# ADSR_7555_MAIN.net
KiCad netlist of a schematic drawn in EAGLE
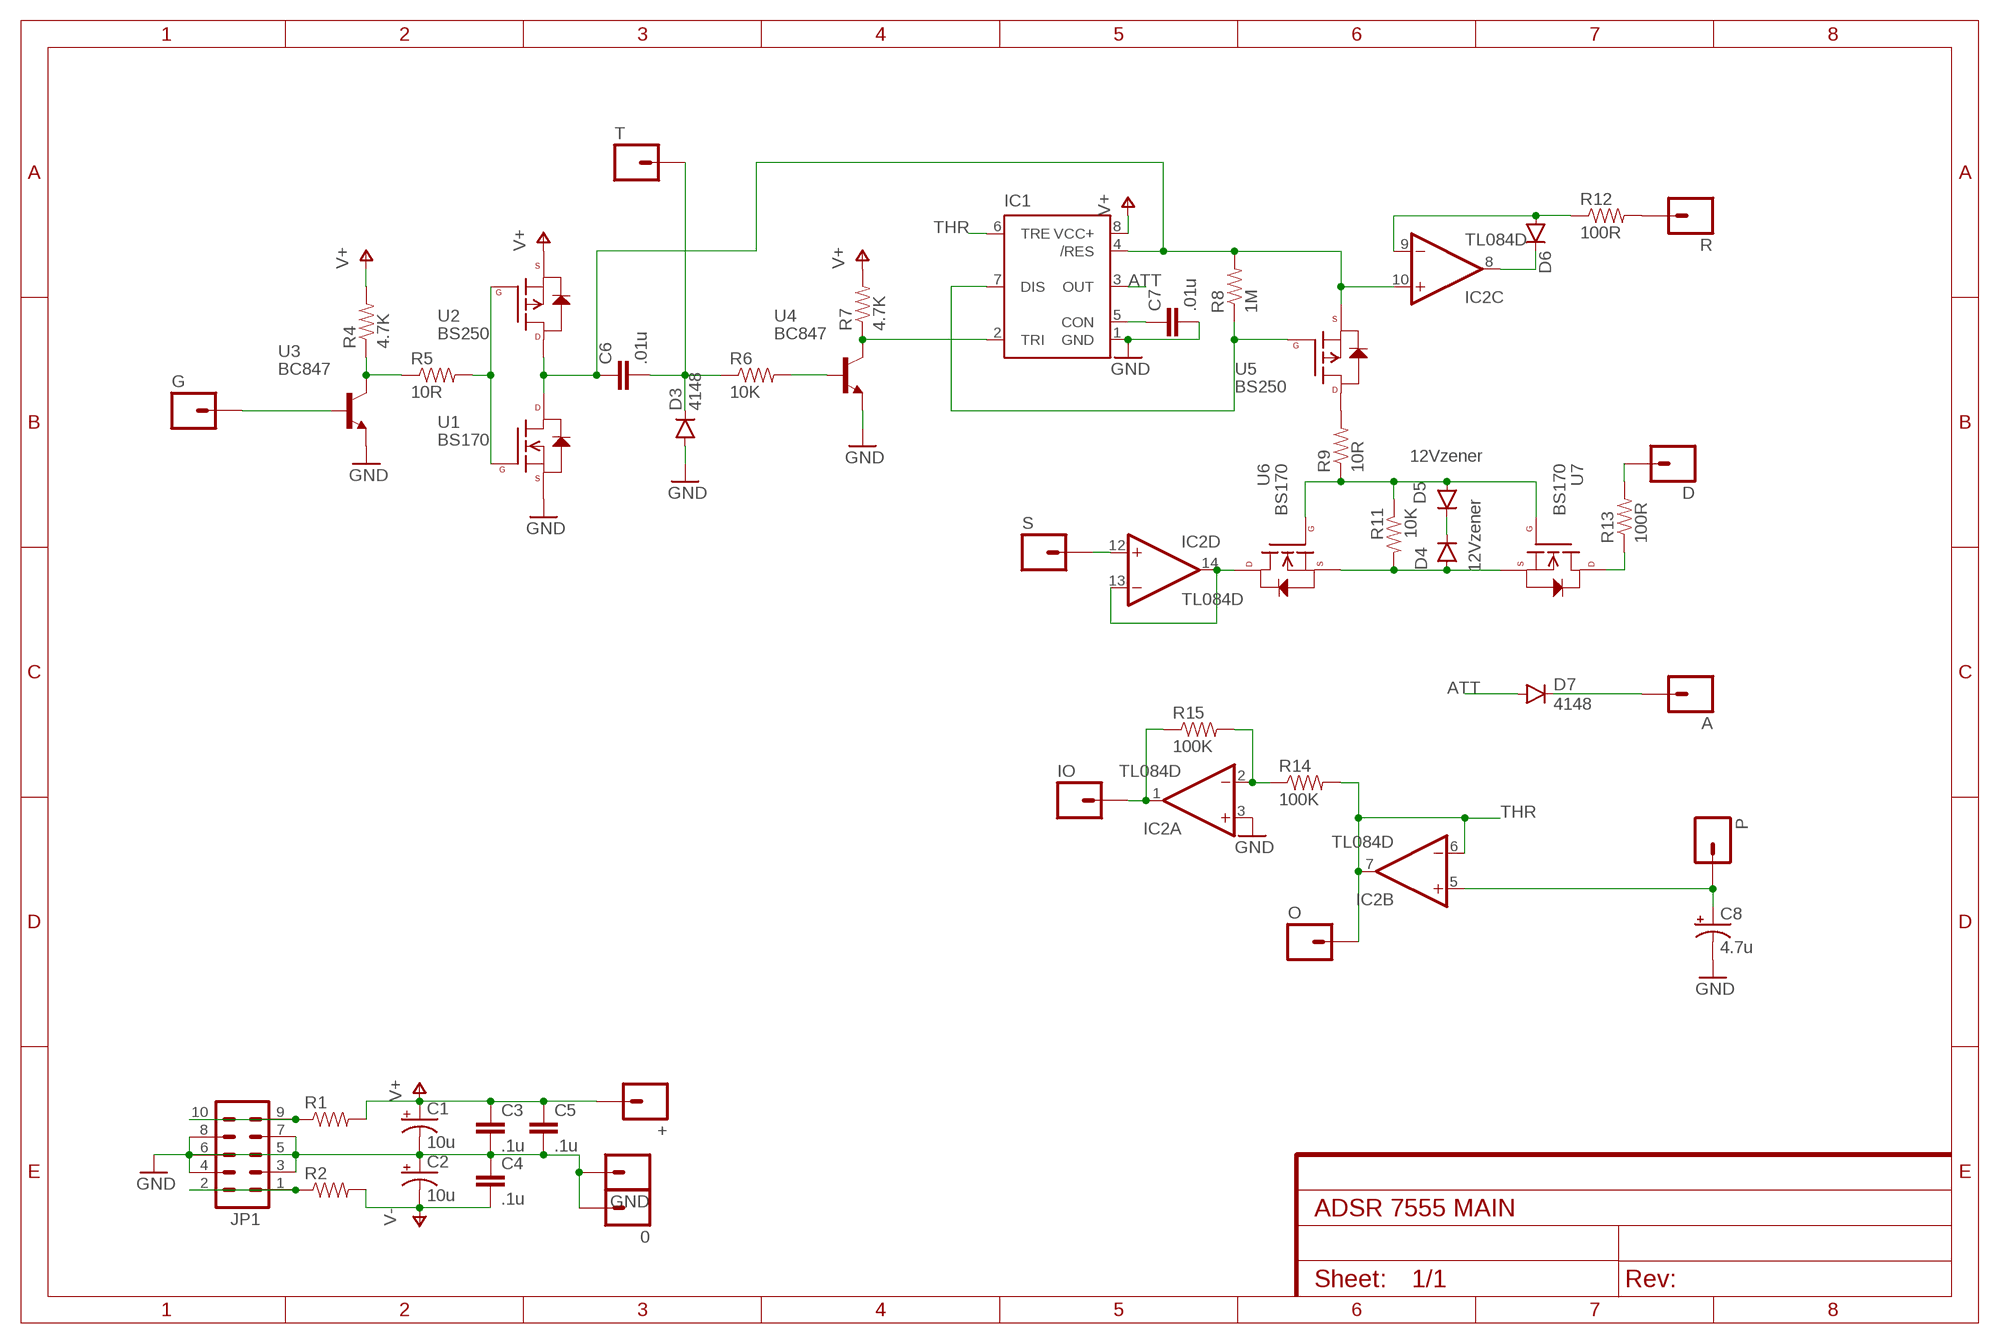
[diagram p0: schematic, sheet 1]

(export (version "E")
  (design (tool "Eeschema 10.0.6"))
  (components
    (comp (ref "+")
      (value "M01PTH")
      (footprint "eagle-import:1X01")
      (libsource (lib "eagle-import") (part "M01PTH"))
    )
    (comp (ref "0")
      (value "M01PTH")
      (footprint "eagle-import:1X01")
      (libsource (lib "eagle-import") (part "M01PTH"))
    )
    (comp (ref "A")
      (value "M01PTH")
      (footprint "eagle-import:1X01")
      (libsource (lib "eagle-import") (part "M01PTH"))
    )
    (comp (ref "C1")
      (value "10u")
      (footprint "eagle-import:CPOL-RADIAL-10UF-25V")
      (libsource (lib "eagle-import") (part "CAP_POLPTH2"))
    )
    (comp (ref "C2")
      (value "10u")
      (footprint "eagle-import:CPOL-RADIAL-10UF-25V")
      (libsource (lib "eagle-import") (part "CAP_POLPTH2"))
    )
    (comp (ref "C3")
      (value ".1u")
      (footprint "eagle-import:0805")
      (libsource (lib "eagle-import") (part "CAP0805"))
    )
    (comp (ref "C4")
      (value ".1u")
      (footprint "eagle-import:0805")
      (libsource (lib "eagle-import") (part "CAP0805"))
    )
    (comp (ref "C5")
      (value ".1u")
      (footprint "eagle-import:0805")
      (libsource (lib "eagle-import") (part "CAP0805"))
    )
    (comp (ref "C6")
      (value ".01u")
      (footprint "eagle-import:0805")
      (libsource (lib "eagle-import") (part "CAP0805"))
    )
    (comp (ref "C7")
      (value ".01u")
      (footprint "eagle-import:0805")
      (libsource (lib "eagle-import") (part "CAP0805"))
    )
    (comp (ref "C8")
      (value "4.7u")
      (footprint "eagle-import:CPOL-RADIAL-10UF-25V")
      (libsource (lib "eagle-import") (part "CAP_POLPTH2"))
    )
    (comp (ref "D")
      (value "M01PTH")
      (footprint "eagle-import:1X01")
      (libsource (lib "eagle-import") (part "M01PTH"))
    )
    (comp (ref "D3")
      (value "4148")
      (footprint "eagle-import:SOD-123")
      (libsource (lib "eagle-import") (part "DIODESOD123"))
    )
    (comp (ref "D4")
      (value "12Vzener")
      (footprint "eagle-import:SOD-123")
      (libsource (lib "eagle-import") (part "DIODESOD123"))
    )
    (comp (ref "D5")
      (value "12Vzener")
      (footprint "eagle-import:SOD-123")
      (libsource (lib "eagle-import") (part "DIODESOD123"))
    )
    (comp (ref "D6")
      (value "DIODESOD123")
      (footprint "eagle-import:SOD-123")
      (libsource (lib "eagle-import") (part "DIODESOD123"))
    )
    (comp (ref "D7")
      (value "4148")
      (footprint "eagle-import:SOD-123")
      (libsource (lib "eagle-import") (part "DIODESOD123"))
    )
    (comp (ref "G")
      (value "M01PTH")
      (footprint "eagle-import:1X01")
      (libsource (lib "eagle-import") (part "M01PTH"))
    )
    (comp (ref "GND")
      (value "M01PTH")
      (footprint "eagle-import:1X01")
      (libsource (lib "eagle-import") (part "M01PTH"))
    )
    (comp (ref "IC1")
      (value "NE555D")
      (footprint "eagle-import:SO08")
      (libsource (lib "eagle-import") (part "NE555D"))
    )
    (comp (ref "IC2")
      (value "TL084D")
      (footprint "eagle-import:SO14")
      (libsource (lib "eagle-import") (part "TL084D"))
    )
    (comp (ref "IO")
      (value "M01PTH")
      (footprint "eagle-import:1X01")
      (libsource (lib "eagle-import") (part "M01PTH"))
    )
    (comp (ref "JP1")
      (value "M05X2PTH")
      (footprint "eagle-import:AVR_ICSP")
      (libsource (lib "eagle-import") (part "M05X2PTH"))
    )
    (comp (ref "O")
      (value "M01PTH")
      (footprint "eagle-import:1X01")
      (libsource (lib "eagle-import") (part "M01PTH"))
    )
    (comp (ref "P")
      (value "M01PTH")
      (footprint "eagle-import:1X01")
      (libsource (lib "eagle-import") (part "M01PTH"))
    )
    (comp (ref "R")
      (value "M01PTH")
      (footprint "eagle-import:1X01")
      (libsource (lib "eagle-import") (part "M01PTH"))
    )
    (comp (ref "R1")
      (value "RESISTOR0805-RES")
      (footprint "eagle-import:0805@1")
      (libsource (lib "eagle-import") (part "RESISTOR0805-RES"))
    )
    (comp (ref "R2")
      (value "RESISTOR0805-RES")
      (footprint "eagle-import:0805@1")
      (libsource (lib "eagle-import") (part "RESISTOR0805-RES"))
    )
    (comp (ref "R4")
      (value "4.7K")
      (footprint "eagle-import:0805@1")
      (libsource (lib "eagle-import") (part "RESISTOR0805-RES"))
    )
    (comp (ref "R5")
      (value "10R")
      (footprint "eagle-import:0805@1")
      (libsource (lib "eagle-import") (part "RESISTOR0805-RES"))
    )
    (comp (ref "R6")
      (value "10K")
      (footprint "eagle-import:0805@1")
      (libsource (lib "eagle-import") (part "RESISTOR0805-RES"))
    )
    (comp (ref "R7")
      (value "4.7K")
      (footprint "eagle-import:0805@1")
      (libsource (lib "eagle-import") (part "RESISTOR0805-RES"))
    )
    (comp (ref "R8")
      (value "1M")
      (footprint "eagle-import:0805@1")
      (libsource (lib "eagle-import") (part "RESISTOR0805-RES"))
    )
    (comp (ref "R9")
      (value "10R")
      (footprint "eagle-import:0805@1")
      (libsource (lib "eagle-import") (part "RESISTOR0805-RES"))
    )
    (comp (ref "R11")
      (value "10K")
      (footprint "eagle-import:0805@1")
      (libsource (lib "eagle-import") (part "RESISTOR0805-RES"))
    )
    (comp (ref "R12")
      (value "100R")
      (footprint "eagle-import:0805@1")
      (libsource (lib "eagle-import") (part "RESISTOR0805-RES"))
    )
    (comp (ref "R13")
      (value "100R")
      (footprint "eagle-import:0805@1")
      (libsource (lib "eagle-import") (part "RESISTOR0805-RES"))
    )
    (comp (ref "R14")
      (value "100K")
      (footprint "eagle-import:0805@1")
      (libsource (lib "eagle-import") (part "RESISTOR0805-RES"))
    )
    (comp (ref "R15")
      (value "100K")
      (footprint "eagle-import:0805@1")
      (libsource (lib "eagle-import") (part "RESISTOR0805-RES"))
    )
    (comp (ref "S")
      (value "M01PTH")
      (footprint "eagle-import:1X01")
      (libsource (lib "eagle-import") (part "M01PTH"))
    )
    (comp (ref "T")
      (value "M01PTH")
      (footprint "eagle-import:1X01")
      (libsource (lib "eagle-import") (part "M01PTH"))
    )
    (comp (ref "U1")
      (value "BS170")
      (footprint "eagle-import:SOT23-3")
      (libsource (lib "eagle-import") (part "N-CHANNEL-MOSFET-BSS138"))
    )
    (comp (ref "U2")
      (value "BS250")
      (footprint "eagle-import:SOT23-3")
      (libsource (lib "eagle-import") (part "P-CHANNEL-MOSFET"))
    )
    (comp (ref "U3")
      (value "BC847")
      (footprint "eagle-import:SOT23")
      (libsource (lib "eagle-import") (part "BC847"))
    )
    (comp (ref "U4")
      (value "BC847")
      (footprint "eagle-import:SOT23")
      (libsource (lib "eagle-import") (part "BC847"))
    )
    (comp (ref "U5")
      (value "BS250")
      (footprint "eagle-import:SOT23-3")
      (libsource (lib "eagle-import") (part "P-CHANNEL-MOSFET"))
    )
    (comp (ref "U6")
      (value "BS170")
      (footprint "eagle-import:SOT23-3")
      (libsource (lib "eagle-import") (part "N-CHANNEL-MOSFET-BSS138"))
    )
    (comp (ref "U7")
      (value "BS170")
      (footprint "eagle-import:SOT23-3")
      (libsource (lib "eagle-import") (part "N-CHANNEL-MOSFET-BSS138"))
    )
  )
  (nets
    (net (code "1") (name "/ATT") (class "Default")
      (node (ref "D7") (pin "A") (pinfunction "A_A") (pintype "passive"))
      (node (ref "IC1") (pin "3") (pinfunction "OUT_3") (pintype "output"))
    )
    (net (code "2") (name "/THR") (class "Default")
      (node (ref "IC1") (pin "6") (pinfunction "TRE_6") (pintype "input"))
      (node (ref "IC2") (pin "6") (pinfunction "-IN_6") (pintype "input"))
      (node (ref "IC2") (pin "7") (pinfunction "OUT_7") (pintype "output"))
      (node (ref "O") (pin "1") (pinfunction "1_1") (pintype "passive"))
      (node (ref "R14") (pin "2") (pinfunction "2_2") (pintype "passive"))
    )
    (net (code "3") (name "GND") (class "Default")
      (node (ref "0") (pin "1") (pinfunction "1_1") (pintype "passive"))
      (node (ref "C1") (pin "2") (pinfunction "-_2") (pintype "passive"))
      (node (ref "C2") (pin "1") (pinfunction "+_1") (pintype "passive"))
      (node (ref "C3") (pin "2") (pinfunction "2_2") (pintype "passive"))
      (node (ref "C4") (pin "1") (pinfunction "1_1") (pintype "passive"))
      (node (ref "C5") (pin "2") (pinfunction "2_2") (pintype "passive"))
      (node (ref "C7") (pin "2") (pinfunction "2_2") (pintype "passive"))
      (node (ref "C8") (pin "2") (pinfunction "-_2") (pintype "passive"))
      (node (ref "D3") (pin "A") (pinfunction "A_A") (pintype "passive"))
      (node (ref "GND") (pin "1") (pinfunction "1_1") (pintype "passive"))
      (node (ref "IC1") (pin "1") (pinfunction "GND_1") (pintype "power_in"))
      (node (ref "IC2") (pin "3") (pinfunction "+IN_3") (pintype "input"))
      (node (ref "JP1") (pin "3") (pinfunction "3_3") (pintype "passive"))
      (node (ref "JP1") (pin "4") (pinfunction "4_4") (pintype "passive"))
      (node (ref "JP1") (pin "5") (pinfunction "5_5") (pintype "passive"))
      (node (ref "JP1") (pin "6") (pinfunction "6_6") (pintype "passive"))
      (node (ref "JP1") (pin "7") (pinfunction "7_7") (pintype "passive"))
      (node (ref "JP1") (pin "8") (pinfunction "8_8") (pintype "passive"))
      (node (ref "U1") (pin "2") (pinfunction "S_2") (pintype "passive"))
      (node (ref "U3") (pin "2") (pinfunction "E_2") (pintype "passive"))
      (node (ref "U4") (pin "2") (pinfunction "E_2") (pintype "passive"))
    )
    (net (code "4") (name "Net-(A-Pad1)") (class "Default")
      (node (ref "A") (pin "1") (pinfunction "1_1") (pintype "passive"))
      (node (ref "D7") (pin "C") (pinfunction "C_C") (pintype "passive"))
    )
    (net (code "5") (name "Net-(C6-Pad2)") (class "Default")
      (node (ref "C6") (pin "2") (pinfunction "2_2") (pintype "passive"))
      (node (ref "D3") (pin "C") (pinfunction "C_C") (pintype "passive"))
      (node (ref "R6") (pin "1") (pinfunction "1_1") (pintype "passive"))
      (node (ref "T") (pin "1") (pinfunction "1_1") (pintype "passive"))
    )
    (net (code "6") (name "Net-(C8-+)") (class "Default")
      (node (ref "C8") (pin "1") (pinfunction "+_1") (pintype "passive"))
      (node (ref "IC2") (pin "5") (pinfunction "+IN_5") (pintype "input"))
      (node (ref "P") (pin "1") (pinfunction "1_1") (pintype "passive"))
    )
    (net (code "7") (name "Net-(D-Pad1)") (class "Default")
      (node (ref "D") (pin "1") (pinfunction "1_1") (pintype "passive"))
      (node (ref "R13") (pin "2") (pinfunction "2_2") (pintype "passive"))
    )
    (net (code "8") (name "Net-(D4-PadC)") (class "Default")
      (node (ref "D4") (pin "C") (pinfunction "C_C") (pintype "passive"))
      (node (ref "D5") (pin "C") (pinfunction "C_C") (pintype "passive"))
    )
    (net (code "9") (name "Net-(IC1-CON)") (class "Default")
      (node (ref "C7") (pin "1") (pinfunction "1_1") (pintype "passive"))
      (node (ref "IC1") (pin "5") (pinfunction "CON_5") (pintype "input"))
    )
    (net (code "10") (name "Net-(IC1-DIS)") (class "Default")
      (node (ref "IC1") (pin "7") (pinfunction "DIS_7") (pintype "input"))
      (node (ref "R8") (pin "1") (pinfunction "1_1") (pintype "passive"))
      (node (ref "U5") (pin "1") (pinfunction "G_1") (pintype "passive"))
    )
    (net (code "11") (name "Net-(IC1-TRI)") (class "Default")
      (node (ref "IC1") (pin "2") (pinfunction "TRI_2") (pintype "input"))
      (node (ref "R7") (pin "1") (pinfunction "1_1") (pintype "passive"))
      (node (ref "U4") (pin "3") (pinfunction "C_3") (pintype "passive"))
    )
    (net (code "12") (name "Net-(IC1-{slash}RES)") (class "Default")
      (node (ref "C6") (pin "1") (pinfunction "1_1") (pintype "passive"))
      (node (ref "IC1") (pin "4") (pinfunction "/RES_4") (pintype "input"))
      (node (ref "IC2") (pin "10") (pinfunction "+IN_10") (pintype "input"))
      (node (ref "R8") (pin "2") (pinfunction "2_2") (pintype "passive"))
      (node (ref "U1") (pin "3") (pinfunction "D_3") (pintype "passive"))
      (node (ref "U2") (pin "3") (pinfunction "D_3") (pintype "passive"))
      (node (ref "U5") (pin "2") (pinfunction "S_2") (pintype "passive"))
    )
    (net (code "13") (name "Net-(IC2A--IN)") (class "Default")
      (node (ref "IC2") (pin "2") (pinfunction "-IN_2") (pintype "input"))
      (node (ref "R14") (pin "1") (pinfunction "1_1") (pintype "passive"))
      (node (ref "R15") (pin "2") (pinfunction "2_2") (pintype "passive"))
    )
    (net (code "14") (name "Net-(IC2A-OUT)") (class "Default")
      (node (ref "IC2") (pin "1") (pinfunction "OUT_1") (pintype "output"))
      (node (ref "IO") (pin "1") (pinfunction "1_1") (pintype "passive"))
      (node (ref "R15") (pin "1") (pinfunction "1_1") (pintype "passive"))
    )
    (net (code "15") (name "Net-(IC2C--IN)") (class "Default")
      (node (ref "D6") (pin "A") (pinfunction "A_A") (pintype "passive"))
      (node (ref "IC2") (pin "9") (pinfunction "-IN_9") (pintype "input"))
      (node (ref "R12") (pin "1") (pinfunction "1_1") (pintype "passive"))
    )
    (net (code "16") (name "Net-(IC2C-OUT)") (class "Default")
      (node (ref "D6") (pin "C") (pinfunction "C_C") (pintype "passive"))
      (node (ref "IC2") (pin "8") (pinfunction "OUT_8") (pintype "output"))
    )
    (net (code "17") (name "Net-(IC2D-+IN)") (class "Default")
      (node (ref "IC2") (pin "12") (pinfunction "+IN_12") (pintype "input"))
      (node (ref "S") (pin "1") (pinfunction "1_1") (pintype "passive"))
    )
    (net (code "18") (name "Net-(IC2D--IN)") (class "Default")
      (node (ref "IC2") (pin "13") (pinfunction "-IN_13") (pintype "input"))
      (node (ref "IC2") (pin "14") (pinfunction "OUT_14") (pintype "output"))
      (node (ref "U6") (pin "3") (pinfunction "D_3") (pintype "passive"))
    )
    (net (code "19") (name "Net-(JP1-Pad1)") (class "Default")
      (node (ref "JP1") (pin "1") (pinfunction "1_1") (pintype "passive"))
      (node (ref "JP1") (pin "2") (pinfunction "2_2") (pintype "passive"))
      (node (ref "R2") (pin "1") (pinfunction "1_1") (pintype "passive"))
    )
    (net (code "20") (name "Net-(JP1-Pad10)") (class "Default")
      (node (ref "JP1") (pin "10") (pinfunction "10_10") (pintype "passive"))
      (node (ref "JP1") (pin "9") (pinfunction "9_9") (pintype "passive"))
      (node (ref "R1") (pin "1") (pinfunction "1_1") (pintype "passive"))
    )
    (net (code "21") (name "Net-(R-Pad1)") (class "Default")
      (node (ref "R") (pin "1") (pinfunction "1_1") (pintype "passive"))
      (node (ref "R12") (pin "2") (pinfunction "2_2") (pintype "passive"))
    )
    (net (code "22") (name "Net-(U1-G)") (class "Default")
      (node (ref "R5") (pin "2") (pinfunction "2_2") (pintype "passive"))
      (node (ref "U1") (pin "1") (pinfunction "G_1") (pintype "passive"))
      (node (ref "U2") (pin "1") (pinfunction "G_1") (pintype "passive"))
    )
    (net (code "23") (name "Net-(U3-B)") (class "Default")
      (node (ref "G") (pin "1") (pinfunction "1_1") (pintype "passive"))
      (node (ref "U3") (pin "1") (pinfunction "B_1") (pintype "passive"))
    )
    (net (code "24") (name "Net-(U3-C)") (class "Default")
      (node (ref "R4") (pin "1") (pinfunction "1_1") (pintype "passive"))
      (node (ref "R5") (pin "1") (pinfunction "1_1") (pintype "passive"))
      (node (ref "U3") (pin "3") (pinfunction "C_3") (pintype "passive"))
    )
    (net (code "25") (name "Net-(U4-B)") (class "Default")
      (node (ref "R6") (pin "2") (pinfunction "2_2") (pintype "passive"))
      (node (ref "U4") (pin "1") (pinfunction "B_1") (pintype "passive"))
    )
    (net (code "26") (name "Net-(U5-D)") (class "Default")
      (node (ref "R9") (pin "2") (pinfunction "2_2") (pintype "passive"))
      (node (ref "U5") (pin "3") (pinfunction "D_3") (pintype "passive"))
    )
    (net (code "27") (name "Net-(U6-G)") (class "Default")
      (node (ref "D5") (pin "A") (pinfunction "A_A") (pintype "passive"))
      (node (ref "R11") (pin "1") (pinfunction "1_1") (pintype "passive"))
      (node (ref "R9") (pin "1") (pinfunction "1_1") (pintype "passive"))
      (node (ref "U6") (pin "1") (pinfunction "G_1") (pintype "passive"))
      (node (ref "U7") (pin "1") (pinfunction "G_1") (pintype "passive"))
    )
    (net (code "28") (name "Net-(U6-S)") (class "Default")
      (node (ref "D4") (pin "A") (pinfunction "A_A") (pintype "passive"))
      (node (ref "R11") (pin "2") (pinfunction "2_2") (pintype "passive"))
      (node (ref "U6") (pin "2") (pinfunction "S_2") (pintype "passive"))
      (node (ref "U7") (pin "2") (pinfunction "S_2") (pintype "passive"))
    )
    (net (code "29") (name "Net-(U7-D)") (class "Default")
      (node (ref "R13") (pin "1") (pinfunction "1_1") (pintype "passive"))
      (node (ref "U7") (pin "3") (pinfunction "D_3") (pintype "passive"))
    )
    (net (code "30") (name "V+") (class "Default")
      (node (ref "+") (pin "1") (pinfunction "1_1") (pintype "passive"))
      (node (ref "C1") (pin "1") (pinfunction "+_1") (pintype "passive"))
      (node (ref "C3") (pin "1") (pinfunction "1_1") (pintype "passive"))
      (node (ref "C5") (pin "1") (pinfunction "1_1") (pintype "passive"))
      (node (ref "IC1") (pin "8") (pinfunction "VCC+_8") (pintype "power_in"))
      (node (ref "R1") (pin "2") (pinfunction "2_2") (pintype "passive"))
      (node (ref "R4") (pin "2") (pinfunction "2_2") (pintype "passive"))
      (node (ref "R7") (pin "2") (pinfunction "2_2") (pintype "passive"))
      (node (ref "U2") (pin "2") (pinfunction "S_2") (pintype "passive"))
    )
    (net (code "31") (name "V-") (class "Default")
      (node (ref "C2") (pin "2") (pinfunction "-_2") (pintype "passive"))
      (node (ref "C4") (pin "2") (pinfunction "2_2") (pintype "passive"))
      (node (ref "R2") (pin "2") (pinfunction "2_2") (pintype "passive"))
    )
  )
)
